# CPU.net
KiCad netlist of a schematic drawn in Altium Designer
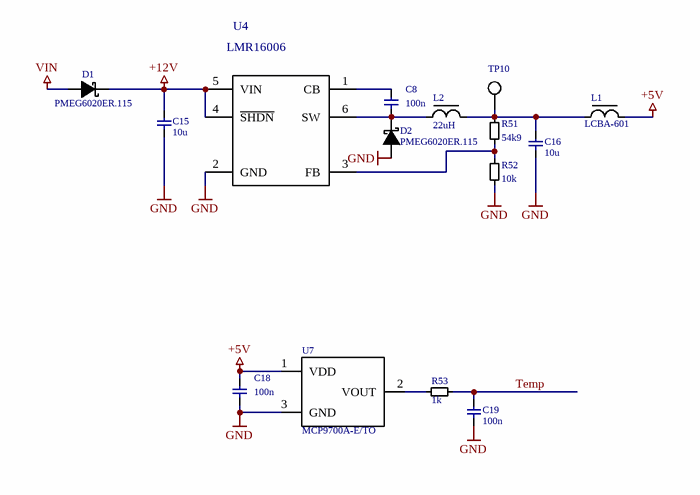
[diagram p0: CPU.SchDoc]

(export (version "E")
  (design (tool "Eeschema 10.0.6"))
  (components
    (comp (ref "C8")
      (value "100n")
      (footprint "C0603")
      (description "Capacitor: ceramic; 100nF; 50V; X7R; ±10%; SMD; 0603; Series: GRM")
      (fields (field (name "MANUFACTURER") "Murata") (field (name "PART NUMBER") "GRM188R71H104KA93D"))
      (libsource (lib "CAPcer") (part "C-013"))
    )
    (comp (ref "C15")
      (value "10u")
      (footprint "C1206")
      (description "Capacitor: ceramic; 10uF; 35V; X7R; ±10%; SMD; 1206")
      (fields (field (name "MANUFACTURER") "Samnsung") (field (name "PART NUMBER") "CL31B106KLHNNNE"))
      (libsource (lib "CAPcer") (part "C-022"))
    )
    (comp (ref "C16")
      (value "10u")
      (footprint "C1206")
      (description "Capacitor: ceramic; 10uF; 35V; X7R; ±10%; SMD; 1206")
      (fields (field (name "MANUFACTURER") "Samnsung") (field (name "PART NUMBER") "CL31B106KLHNNNE"))
      (libsource (lib "CAPcer") (part "C-022"))
    )
    (comp (ref "C18")
      (value "100n")
      (footprint "C0603")
      (description "Capacitor: ceramic; 100nF; 50V; X7R; ±10%; SMD; 0603; Series: GRM")
      (fields (field (name "MANUFACTURER") "Murata") (field (name "PART NUMBER") "GRM188R71H104KA93D"))
      (libsource (lib "CAPcer") (part "C-013"))
    )
    (comp (ref "C19")
      (value "100n")
      (footprint "C0603")
      (description "Capacitor: ceramic; 100nF; 50V; X7R; ±10%; SMD; 0603; Series: GRM")
      (fields (field (name "MANUFACTURER") "Murata") (field (name "PART NUMBER") "GRM188R71H104KA93D"))
      (libsource (lib "CAPcer") (part "C-013"))
    )
    (comp (ref "D1")
      (value "PMEG6020ER.115")
      (footprint "SOD123")
      (description "Diode: Schottky rectifying; SMD; 60V; 2A; SOD123W")
      (fields (field (name "MANUFACTURER") "Nexperia"))
      (libsource (lib "Diodes") (part "STPS2H100A"))
    )
    (comp (ref "D2")
      (value "PMEG6020ER.115")
      (footprint "SOD123")
      (description "Diode: Schottky rectifying; SMD; 60V; 2A; SOD123W")
      (fields (field (name "MANUFACTURER") "Nexperia"))
      (libsource (lib "Diodes") (part "STPS2H100A"))
    )
    (comp (ref "L1")
      (value "LCBA-601")
      (footprint "R0603")
      (description "Ferrite: bead; Imp.@ 100MHz:600Ohm; Mounting: SMD; 1A; Case:0603")
      (fields (field (name "MANUFACTURER") "Ferrocore"))
      (libsource (lib "WH") (part "LCBA-601"))
    )
    (comp (ref "L2")
      (value "22uH")
      (footprint "L4040")
      (description "Inductor: wire; SMD; 1515; 22uH; 790mA; 0.37R; 4x4x1.65mm")
      (fields (field (name "MANUFACTURER") "Murata") (field (name "PART NUMBER") "LQH44PN220MP0L"))
      (libsource (lib "WH") (part "L4040"))
    )
    (comp (ref "R51")
      (value "54k9")
      (footprint "R0603")
      (description "Resistor: thick film; SMD; 0603; 54.9k; 0.1W; ±1%;")
      (fields (field (name "MANUFACTURER") "Yageo") (field (name "PART NUMBER") "RC0603FR-0754K9L"))
      (libsource (lib "Resistors") (part "R-016"))
    )
    (comp (ref "R52")
      (value "10k")
      (footprint "R0603")
      (description "Resistor: thick film; SMD; 0603; 10k; 0.125W; ±5%")
      (fields (field (name "MANUFACTURER") "Walsin") (field (name "PART NUMBER") "WF06P103JTL"))
      (libsource (lib "Resistors") (part "R-012"))
    )
    (comp (ref "R53")
      (value "1k")
      (footprint "R0603")
      (description "Resistor: thick film; SMD; 0603; 1k; 0.1W; ±5%")
      (fields (field (name "MANUFACTURER") "Royal Ohm") (field (name "PART NUMBER") "0603SAJ0102T5E"))
      (libsource (lib "Resistors") (part "R-005"))
    )
    (comp (ref "TP10")
      (value "TP")
      (footprint "TP")
      (description "Test point")
      (libsource (lib "DGI") (part "TP"))
    )
    (comp (ref "U4")
      (value "LMR16006")
      (footprint "SOT-23-6")
      (description "60 V 0.6 A Buck Regulators With High Efficiency ECO  Mode")
      (fields (field (name "MANUFACTURER") "ST") (field (name "PART NUMBER") "LMR16006XDDCR"))
      (libsource (lib "WH") (part "LMR16006"))
    )
    (comp (ref "U7")
      (value "MCP9700A-E/TO")
      (footprint "TO-92A")
      (description "Czujnik temperatury; przetwornik temperatury; -40÷150°C; TO92")
      (fields (field (name "MANUFACTURER") "Microchip"))
      (libsource (lib "WH") (part "MCP9700 - TO-92"))
    )
  )
  (nets
    (net (code "1") (name "+5V") (class "Default")
      (node (ref "C18") (pin "1") (pinfunction "1_1") (pintype "passive"))
      (node (ref "L1") (pin "2") (pinfunction "2_2") (pintype "passive"))
      (node (ref "U7") (pin "1") (pinfunction "VDD_1") (pintype "passive"))
    )
    (net (code "2") (name "+12V") (class "Default")
      (node (ref "C15") (pin "1") (pinfunction "1_1") (pintype "passive"))
      (node (ref "D1") (pin "2") (pinfunction "K_2") (pintype "passive"))
      (node (ref "U4") (pin "4") (pinfunction "~{SHDN}_4") (pintype "passive"))
      (node (ref "U4") (pin "5") (pinfunction "VIN_5") (pintype "passive"))
    )
    (net (code "3") (name "/Temp") (class "Default")
      (node (ref "C19") (pin "1") (pinfunction "1_1") (pintype "passive"))
      (node (ref "R53") (pin "1") (pinfunction "TOP_1") (pintype "passive"))
    )
    (net (code "4") (name "GND") (class "Default")
      (node (ref "C15") (pin "2") (pinfunction "2_2") (pintype "passive"))
      (node (ref "C16") (pin "2") (pinfunction "2_2") (pintype "passive"))
      (node (ref "C18") (pin "2") (pinfunction "2_2") (pintype "passive"))
      (node (ref "C19") (pin "2") (pinfunction "2_2") (pintype "passive"))
      (node (ref "D2") (pin "1") (pinfunction "A_1") (pintype "passive"))
      (node (ref "R52") (pin "1") (pinfunction "TOP_1") (pintype "passive"))
      (node (ref "U4") (pin "2") (pinfunction "GND_2") (pintype "passive"))
      (node (ref "U7") (pin "3") (pinfunction "GND_3") (pintype "passive"))
    )
    (net (code "5") (name "Net-(D2-K)") (class "Default")
      (node (ref "C8") (pin "2") (pinfunction "2_2") (pintype "passive"))
      (node (ref "D2") (pin "2") (pinfunction "K_2") (pintype "passive"))
      (node (ref "L2") (pin "1") (pinfunction "1_1") (pintype "passive"))
      (node (ref "U4") (pin "6") (pinfunction "SW_6") (pintype "passive"))
    )
    (net (code "6") (name "Net-(R51-BOT)") (class "Default")
      (node (ref "C16") (pin "1") (pinfunction "1_1") (pintype "passive"))
      (node (ref "L1") (pin "1") (pinfunction "1_1") (pintype "passive"))
      (node (ref "L2") (pin "2") (pinfunction "2_2") (pintype "passive"))
      (node (ref "R51") (pin "2") (pinfunction "BOT_2") (pintype "passive"))
      (node (ref "TP10") (pin "1") (pinfunction "1_1") (pintype "passive"))
    )
    (net (code "7") (name "Net-(R51-TOP)") (class "Default")
      (node (ref "R51") (pin "1") (pinfunction "TOP_1") (pintype "passive"))
      (node (ref "R52") (pin "2") (pinfunction "BOT_2") (pintype "passive"))
      (node (ref "U4") (pin "3") (pinfunction "FB_3") (pintype "passive"))
    )
    (net (code "8") (name "Net-(R53-BOT)") (class "Default")
      (node (ref "R53") (pin "2") (pinfunction "BOT_2") (pintype "passive"))
      (node (ref "U7") (pin "2") (pinfunction "VOUT_2") (pintype "passive"))
    )
    (net (code "9") (name "Net-(U4-CB)") (class "Default")
      (node (ref "C8") (pin "1") (pinfunction "1_1") (pintype "passive"))
      (node (ref "U4") (pin "1") (pinfunction "CB_1") (pintype "passive"))
    )
    (net (code "10") (name "VIN") (class "Default")
      (node (ref "D1") (pin "1") (pinfunction "A_1") (pintype "passive"))
    )
  )
)
